# Hello_World.net
KiCad netlist of a schematic drawn in EAGLE
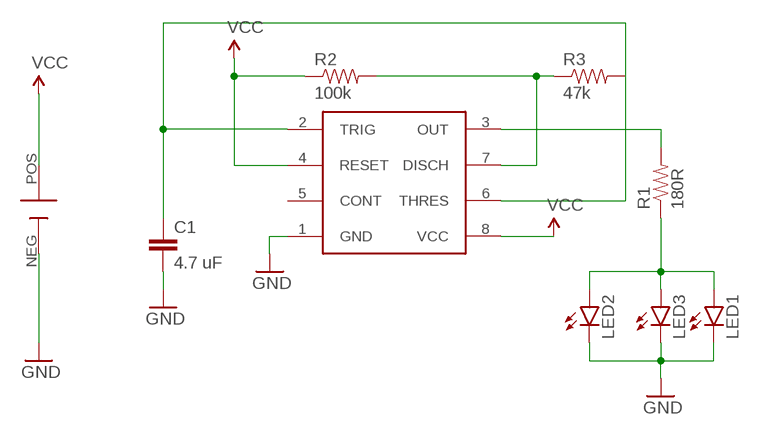
[diagram p0: schematic, sheet 1]

(export (version "E")
  (design (tool "Eeschema 10.0.6"))
  (components
    (comp (ref "C1")
      (value "4.7 uF")
      (footprint "eagle-import:C1206")
      (libsource (lib "eagle-import") (part "C-EUC1206"))
    )
    (comp (ref "LED1")
      (value "LED1206")
      (footprint "eagle-import:LED-1206")
      (libsource (lib "eagle-import") (part "LED1206"))
    )
    (comp (ref "LED2")
      (value "LED1206")
      (footprint "eagle-import:LED-1206")
      (libsource (lib "eagle-import") (part "LED1206"))
    )
    (comp (ref "LED3")
      (value "LED1206")
      (footprint "eagle-import:LED-1206")
      (libsource (lib "eagle-import") (part "LED1206"))
    )
    (comp (ref "R1")
      (value "180R")
      (footprint "eagle-import:1206")
      (libsource (lib "eagle-import") (part "RESISTOR1206"))
    )
    (comp (ref "R2")
      (value "100k")
      (footprint "eagle-import:1206")
      (libsource (lib "eagle-import") (part "RESISTOR1206"))
    )
    (comp (ref "R3")
      (value "47k")
      (footprint "eagle-import:1206")
      (libsource (lib "eagle-import") (part "RESISTOR1206"))
    )
    (comp (ref "U$1")
      (value "SMD_BATTERY_9V")
      (footprint "eagle-import:SMD_BATTERY_PADS")
      (libsource (lib "eagle-import") (part "SMD_BATTERY_9V"))
    )
    (comp (ref "U1")
      (value "NE555PSR")
      (footprint "eagle-import:PS_R-PDSO-G8")
      (libsource (lib "eagle-import") (part "NE555PSR"))
    )
  )
  (nets
    (net (code "1") (name "GND") (class "Default")
      (node (ref "C1") (pin "2") (pinfunction "2_2") (pintype "passive"))
      (node (ref "LED1") (pin "C") (pinfunction "C_C") (pintype "passive"))
      (node (ref "LED2") (pin "C") (pinfunction "C_C") (pintype "passive"))
      (node (ref "LED3") (pin "C") (pinfunction "C_C") (pintype "passive"))
      (node (ref "U$1") (pin "NEG") (pinfunction "NEG_NEG") (pintype "bidirectional"))
      (node (ref "U1") (pin "1") (pinfunction "GND_1") (pintype "bidirectional"))
    )
    (net (code "2") (name "Net-(LED1-PadA)") (class "Default")
      (node (ref "LED1") (pin "A") (pinfunction "A_A") (pintype "passive"))
      (node (ref "LED2") (pin "A") (pinfunction "A_A") (pintype "passive"))
      (node (ref "LED3") (pin "A") (pinfunction "A_A") (pintype "passive"))
      (node (ref "R1") (pin "1") (pinfunction "1_1") (pintype "passive"))
    )
    (net (code "3") (name "Net-(U1-DISCH)") (class "Default")
      (node (ref "R2") (pin "2") (pinfunction "2_2") (pintype "passive"))
      (node (ref "R3") (pin "1") (pinfunction "1_1") (pintype "passive"))
      (node (ref "U1") (pin "7") (pinfunction "DISCH_7") (pintype "bidirectional"))
    )
    (net (code "4") (name "Net-(U1-OUT)") (class "Default")
      (node (ref "R1") (pin "2") (pinfunction "2_2") (pintype "passive"))
      (node (ref "U1") (pin "3") (pinfunction "OUT_3") (pintype "bidirectional"))
    )
    (net (code "5") (name "Net-(U1-THRES)") (class "Default")
      (node (ref "C1") (pin "1") (pinfunction "1_1") (pintype "passive"))
      (node (ref "R3") (pin "2") (pinfunction "2_2") (pintype "passive"))
      (node (ref "U1") (pin "2") (pinfunction "TRIG_2") (pintype "bidirectional"))
      (node (ref "U1") (pin "6") (pinfunction "THRES_6") (pintype "bidirectional"))
    )
    (net (code "6") (name "VCC") (class "Default")
      (node (ref "R2") (pin "1") (pinfunction "1_1") (pintype "passive"))
      (node (ref "U$1") (pin "POS") (pinfunction "POS_POS") (pintype "bidirectional"))
      (node (ref "U1") (pin "4") (pinfunction "RESET_4") (pintype "bidirectional"))
      (node (ref "U1") (pin "8") (pinfunction "VCC_8") (pintype "bidirectional"))
    )
    (net (code "7") (name "unconnected-(U1-CONT-Pad5)") (class "Default")
      (node (ref "U1") (pin "5") (pinfunction "CONT_5") (pintype "bidirectional"))
    )
  )
)
